# PiedPiper.net
KiCad netlist of a schematic drawn in EAGLE
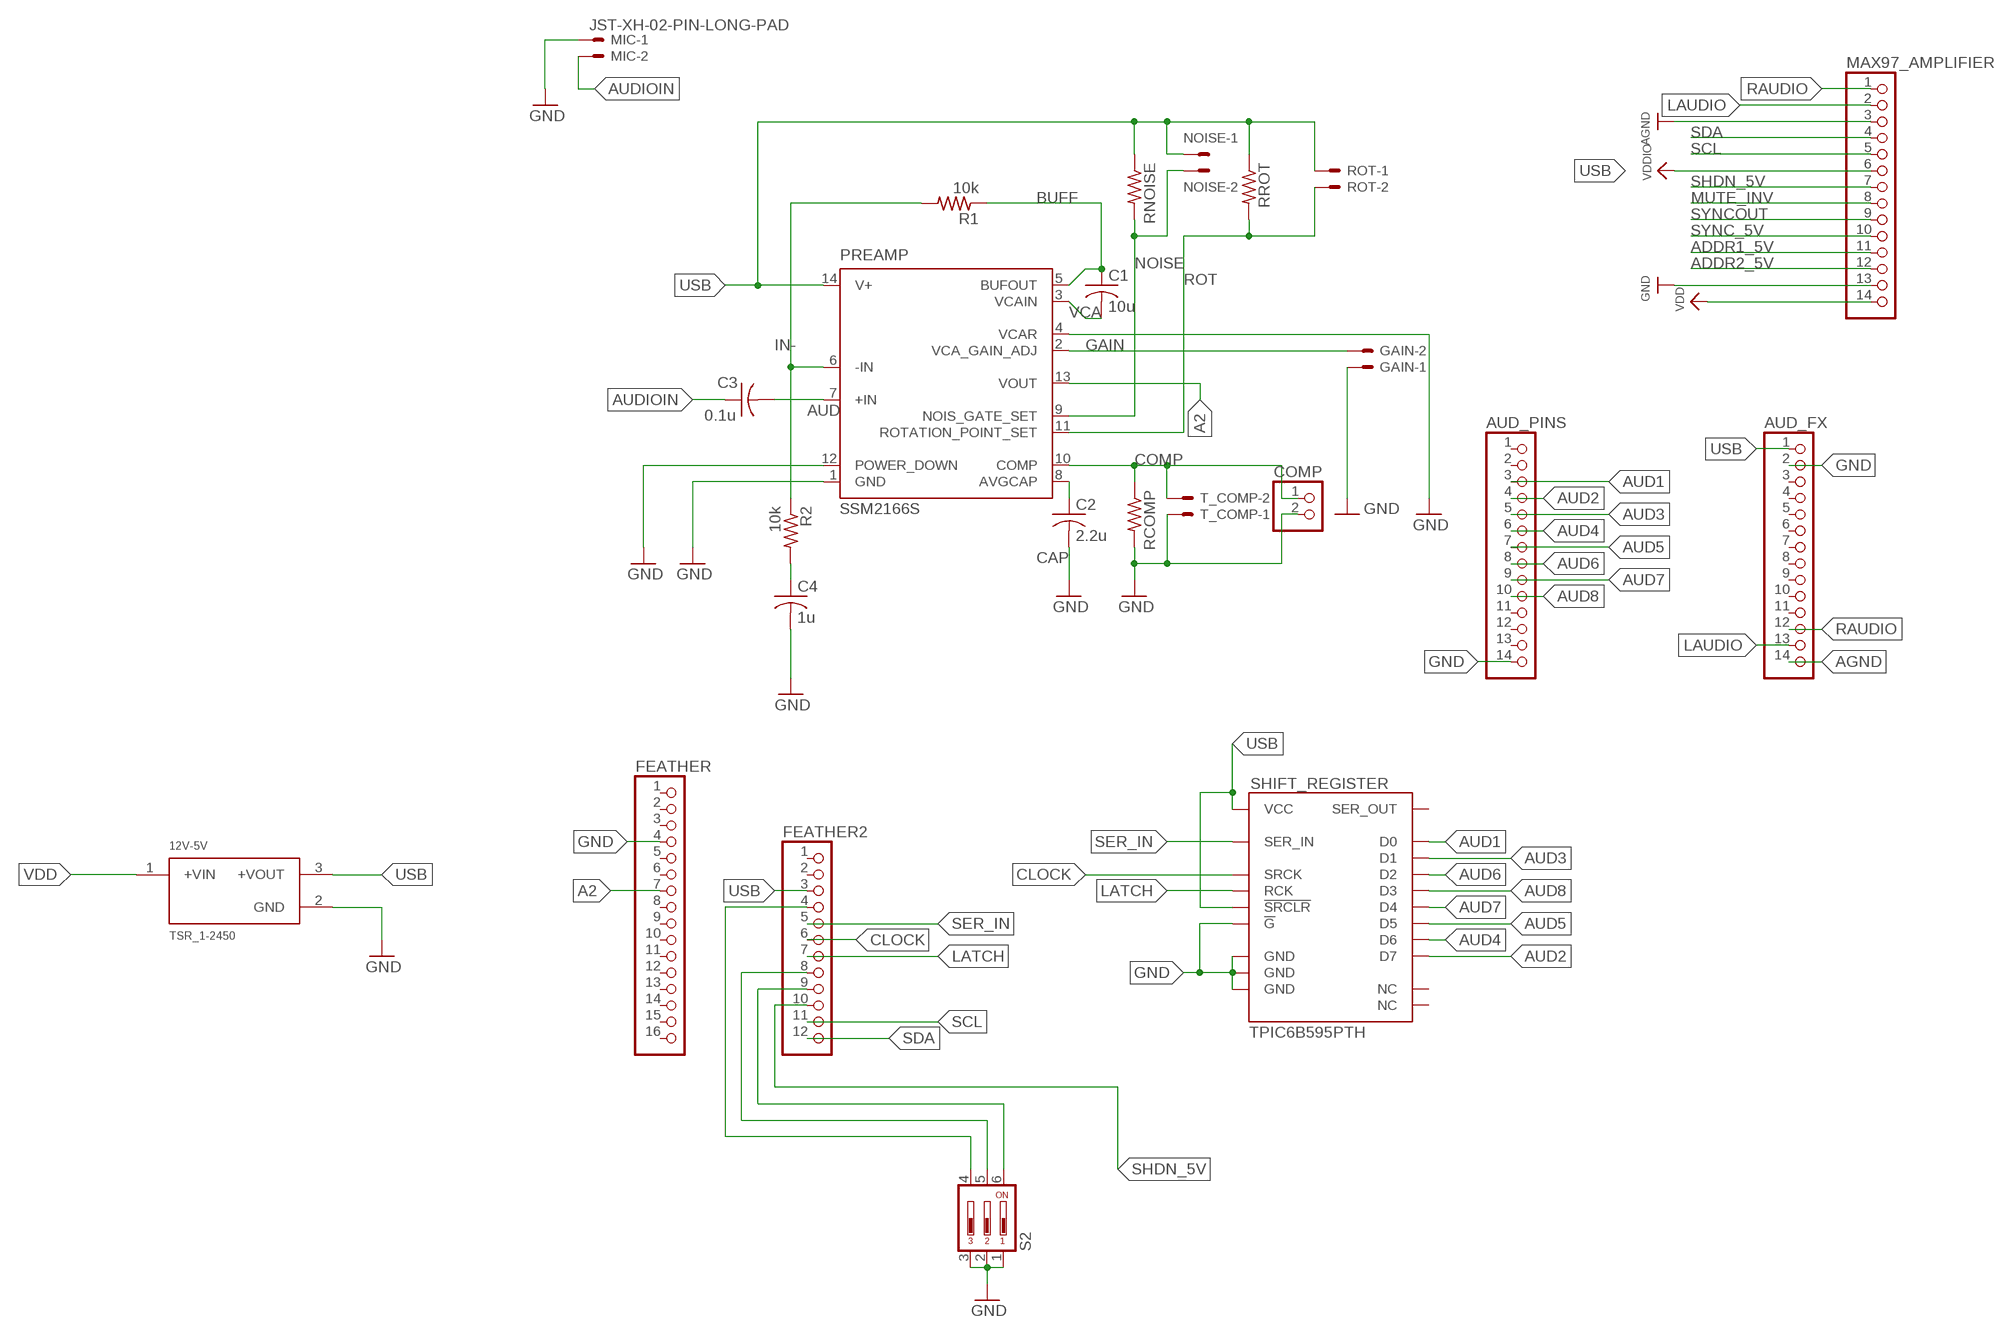
[diagram p0: schematic, sheet 1]

(export (version "E")
  (design (tool "Eeschema 10.0.6"))
  (components
    (comp (ref "12V-5V")
      (value "TSR_1-2450")
      (footprint "eagle-import:CONV_TSR_1-2450")
      (fields (field (name "MF") "Traco Power") (field (name "MP") "TSR 1-2450"))
      (libsource (lib "eagle-import") (part "TSR_1-2450"))
    )
    (comp (ref "AUD_FX")
      (value "PINHD-1X14")
      (footprint "eagle-import:1X14")
      (libsource (lib "eagle-import") (part "PINHD-1X14"))
    )
    (comp (ref "AUD_PINS")
      (value "PINHD-1X14")
      (footprint "eagle-import:1X14")
      (libsource (lib "eagle-import") (part "PINHD-1X14"))
    )
    (comp (ref "C1")
      (value "10u")
      (footprint "eagle-import:C0805")
      (libsource (lib "eagle-import") (part "C-USC0805"))
    )
    (comp (ref "C2")
      (value "2.2u")
      (footprint "eagle-import:C0805")
      (libsource (lib "eagle-import") (part "C-USC0805"))
    )
    (comp (ref "C3")
      (value "0.1u")
      (footprint "eagle-import:C0805")
      (libsource (lib "eagle-import") (part "C-USC0805"))
    )
    (comp (ref "C4")
      (value "1u")
      (footprint "eagle-import:C0805")
      (libsource (lib "eagle-import") (part "C-USC0805"))
    )
    (comp (ref "COMP")
      (value "PINHD-1X2")
      (footprint "eagle-import:1X02")
      (libsource (lib "eagle-import") (part "PINHD-1X2"))
    )
    (comp (ref "FEATHER")
      (value "PINHD-1X16")
      (footprint "eagle-import:1X16")
      (libsource (lib "eagle-import") (part "PINHD-1X16"))
    )
    (comp (ref "FEATHER2")
      (value "PINHD-1X12")
      (footprint "eagle-import:1X12")
      (libsource (lib "eagle-import") (part "PINHD-1X12"))
    )
    (comp (ref "GAIN")
      (value "JST-XH-02-PIN-LONG-PAD")
      (footprint "eagle-import:JST-XH-02-PACKAGE-LONG-PAD")
      (libsource (lib "eagle-import") (part "JST-XH-02-PIN-LONG-PAD"))
    )
    (comp (ref "MAX97_AMPLIFIER")
      (value "HEADER-1X14")
      (footprint "eagle-import:1X14_ROUND70")
      (libsource (lib "eagle-import") (part "HEADER-1X14"))
    )
    (comp (ref "MIC")
      (value "JST-XH-02-PIN-LONG-PAD")
      (footprint "eagle-import:JST-XH-02-PACKAGE-LONG-PAD")
      (libsource (lib "eagle-import") (part "JST-XH-02-PIN-LONG-PAD"))
    )
    (comp (ref "NOISE")
      (value "JST-XH-02-PIN-LONG-PAD")
      (footprint "eagle-import:JST-XH-02-PACKAGE-LONG-PAD")
      (libsource (lib "eagle-import") (part "JST-XH-02-PIN-LONG-PAD"))
    )
    (comp (ref "PREAMP")
      (value "SSM2166S")
      (footprint "eagle-import:SO14")
      (fields (field (name "MF") "Analog Devices") (field (name "MP") "SSM2166"))
      (libsource (lib "eagle-import") (part "SSM2166S"))
    )
    (comp (ref "R1")
      (value "10k")
      (footprint "eagle-import:R1206")
      (libsource (lib "eagle-import") (part "R-US_R1206"))
    )
    (comp (ref "R2")
      (value "10k")
      (footprint "eagle-import:R1206")
      (libsource (lib "eagle-import") (part "R-US_R1206"))
    )
    (comp (ref "RCOMP")
      (value "R-US_R1206")
      (footprint "eagle-import:R1206")
      (libsource (lib "eagle-import") (part "R-US_R1206"))
    )
    (comp (ref "RNOISE")
      (value "R-US_R1206")
      (footprint "eagle-import:R1206")
      (libsource (lib "eagle-import") (part "R-US_R1206"))
    )
    (comp (ref "ROT")
      (value "JST-XH-02-PIN-LONG-PAD")
      (footprint "eagle-import:JST-XH-02-PACKAGE-LONG-PAD")
      (libsource (lib "eagle-import") (part "JST-XH-02-PIN-LONG-PAD"))
    )
    (comp (ref "RROT")
      (value "R-US_R1206")
      (footprint "eagle-import:R1206")
      (libsource (lib "eagle-import") (part "R-US_R1206"))
    )
    (comp (ref "S2")
      (value "DP03")
      (footprint "eagle-import:DP-03")
      (fields (field (name "MPN") "MCDP03"))
      (libsource (lib "eagle-import") (part "DP03"))
    )
    (comp (ref "SHIFT_REGISTER")
      (value "TPIC6B595PTH")
      (footprint "eagle-import:DIL20")
      (fields (field (name "MF") "Texas Instruments") (field (name "MP") "TPIC6B595"))
      (libsource (lib "eagle-import") (part "TPIC6B595PTH"))
    )
    (comp (ref "T_COMP")
      (value "JST-XH-02-PIN-LONG-PAD")
      (footprint "eagle-import:JST-XH-02-PACKAGE-LONG-PAD")
      (libsource (lib "eagle-import") (part "JST-XH-02-PIN-LONG-PAD"))
    )
  )
  (nets
    (net (code "1") (name "/ADDR1_5V") (class "Default")
      (node (ref "MAX97_AMPLIFIER") (pin "11") (pinfunction "11_11") (pintype "passive"))
    )
    (net (code "2") (name "/ADDR2_5V") (class "Default")
      (node (ref "MAX97_AMPLIFIER") (pin "12") (pinfunction "12_12") (pintype "passive"))
    )
    (net (code "3") (name "/AUD") (class "Default")
      (node (ref "C3") (pin "2") (pinfunction "2_2") (pintype "passive"))
      (node (ref "PREAMP") (pin "7") (pinfunction "+IN_7") (pintype "input"))
    )
    (net (code "4") (name "/BUFF") (class "Default")
      (node (ref "C1") (pin "1") (pinfunction "1_1") (pintype "passive"))
      (node (ref "PREAMP") (pin "5") (pinfunction "BUFOUT_5") (pintype "output"))
      (node (ref "R1") (pin "1") (pinfunction "1_1") (pintype "passive"))
    )
    (net (code "5") (name "/CAP") (class "Default")
      (node (ref "C2") (pin "1") (pinfunction "1_1") (pintype "passive"))
      (node (ref "PREAMP") (pin "8") (pinfunction "AVGCAP_8") (pintype "passive"))
    )
    (net (code "6") (name "/COMP") (class "Default")
      (node (ref "COMP") (pin "1") (pinfunction "1_1") (pintype "passive"))
      (node (ref "PREAMP") (pin "10") (pinfunction "COMP_10") (pintype "passive"))
      (node (ref "RCOMP") (pin "1") (pinfunction "1_1") (pintype "passive"))
      (node (ref "T_COMP") (pin "2") (pinfunction "S_2") (pintype "passive"))
    )
    (net (code "7") (name "/GAIN") (class "Default")
      (node (ref "GAIN") (pin "2") (pinfunction "S_2") (pintype "passive"))
      (node (ref "PREAMP") (pin "2") (pinfunction "VCA_GAIN_ADJ_2") (pintype "input"))
    )
    (net (code "8") (name "/IN-") (class "Default")
      (node (ref "PREAMP") (pin "6") (pinfunction "-IN_6") (pintype "input"))
      (node (ref "R1") (pin "2") (pinfunction "2_2") (pintype "passive"))
      (node (ref "R2") (pin "1") (pinfunction "1_1") (pintype "passive"))
    )
    (net (code "9") (name "/MUTE_INV") (class "Default")
      (node (ref "MAX97_AMPLIFIER") (pin "8") (pinfunction "8_8") (pintype "passive"))
    )
    (net (code "10") (name "/NOISE") (class "Default")
      (node (ref "NOISE") (pin "2") (pinfunction "S_2") (pintype "passive"))
      (node (ref "PREAMP") (pin "9") (pinfunction "NOIS_GATE_SET_9") (pintype "passive"))
      (node (ref "RNOISE") (pin "2") (pinfunction "2_2") (pintype "passive"))
    )
    (net (code "11") (name "/ROT") (class "Default")
      (node (ref "PREAMP") (pin "11") (pinfunction "ROTATION_POINT_SET_11") (pintype "passive"))
      (node (ref "ROT") (pin "2") (pinfunction "S_2") (pintype "passive"))
      (node (ref "RROT") (pin "2") (pinfunction "2_2") (pintype "passive"))
    )
    (net (code "12") (name "/SYNCOUT") (class "Default")
      (node (ref "MAX97_AMPLIFIER") (pin "9") (pinfunction "9_9") (pintype "passive"))
    )
    (net (code "13") (name "/SYNC_5V") (class "Default")
      (node (ref "MAX97_AMPLIFIER") (pin "10") (pinfunction "10_10") (pintype "passive"))
    )
    (net (code "14") (name "/VCA") (class "Default")
      (node (ref "C1") (pin "2") (pinfunction "2_2") (pintype "passive"))
      (node (ref "PREAMP") (pin "3") (pinfunction "VCAIN_3") (pintype "input"))
    )
    (net (code "15") (name "A2") (class "Default")
      (node (ref "FEATHER") (pin "7") (pinfunction "7_7") (pintype "passive"))
      (node (ref "PREAMP") (pin "13") (pinfunction "VOUT_13") (pintype "output"))
    )
    (net (code "16") (name "AGND") (class "Default")
      (node (ref "AUD_FX") (pin "14") (pinfunction "14_14") (pintype "passive"))
      (node (ref "MAX97_AMPLIFIER") (pin "3") (pinfunction "3_3") (pintype "passive"))
    )
    (net (code "17") (name "AUD1") (class "Default")
      (node (ref "AUD_PINS") (pin "3") (pinfunction "3_3") (pintype "passive"))
      (node (ref "SHIFT_REGISTER") (pin "4") (pinfunction "D0_4") (pintype "output"))
    )
    (net (code "18") (name "AUD2") (class "Default")
      (node (ref "AUD_PINS") (pin "4") (pinfunction "4_4") (pintype "passive"))
      (node (ref "SHIFT_REGISTER") (pin "17") (pinfunction "D7_17") (pintype "output"))
    )
    (net (code "19") (name "AUD3") (class "Default")
      (node (ref "AUD_PINS") (pin "5") (pinfunction "5_5") (pintype "passive"))
      (node (ref "SHIFT_REGISTER") (pin "5") (pinfunction "D1_5") (pintype "output"))
    )
    (net (code "20") (name "AUD4") (class "Default")
      (node (ref "AUD_PINS") (pin "6") (pinfunction "6_6") (pintype "passive"))
      (node (ref "SHIFT_REGISTER") (pin "16") (pinfunction "D6_16") (pintype "output"))
    )
    (net (code "21") (name "AUD5") (class "Default")
      (node (ref "AUD_PINS") (pin "7") (pinfunction "7_7") (pintype "passive"))
      (node (ref "SHIFT_REGISTER") (pin "15") (pinfunction "D5_15") (pintype "output"))
    )
    (net (code "22") (name "AUD6") (class "Default")
      (node (ref "AUD_PINS") (pin "8") (pinfunction "8_8") (pintype "passive"))
      (node (ref "SHIFT_REGISTER") (pin "6") (pinfunction "D2_6") (pintype "output"))
    )
    (net (code "23") (name "AUD7") (class "Default")
      (node (ref "AUD_PINS") (pin "9") (pinfunction "9_9") (pintype "passive"))
      (node (ref "SHIFT_REGISTER") (pin "14") (pinfunction "D4_14") (pintype "output"))
    )
    (net (code "24") (name "AUD8") (class "Default")
      (node (ref "AUD_PINS") (pin "10") (pinfunction "10_10") (pintype "passive"))
      (node (ref "SHIFT_REGISTER") (pin "7") (pinfunction "D3_7") (pintype "output"))
    )
    (net (code "25") (name "AUDIOIN") (class "Default")
      (node (ref "C3") (pin "1") (pinfunction "1_1") (pintype "passive"))
      (node (ref "MIC") (pin "2") (pinfunction "S_2") (pintype "passive"))
    )
    (net (code "26") (name "CLOCK") (class "Default")
      (node (ref "FEATHER2") (pin "6") (pinfunction "6_6") (pintype "passive"))
      (node (ref "SHIFT_REGISTER") (pin "13") (pinfunction "SRCK_13") (pintype "input"))
    )
    (net (code "27") (name "GND") (class "Default")
      (node (ref "12V-5V") (pin "2") (pinfunction "GND_2") (pintype "power_in"))
      (node (ref "AUD_FX") (pin "2") (pinfunction "2_2") (pintype "passive"))
      (node (ref "AUD_PINS") (pin "14") (pinfunction "14_14") (pintype "passive"))
      (node (ref "C2") (pin "2") (pinfunction "2_2") (pintype "passive"))
      (node (ref "C4") (pin "2") (pinfunction "2_2") (pintype "passive"))
      (node (ref "COMP") (pin "2") (pinfunction "2_2") (pintype "passive"))
      (node (ref "FEATHER") (pin "4") (pinfunction "4_4") (pintype "passive"))
      (node (ref "GAIN") (pin "1") (pinfunction "S_1") (pintype "passive"))
      (node (ref "MAX97_AMPLIFIER") (pin "13") (pinfunction "13_13") (pintype "passive"))
      (node (ref "MIC") (pin "1") (pinfunction "S_1") (pintype "passive"))
      (node (ref "PREAMP") (pin "1") (pinfunction "GND_1") (pintype "power_in"))
      (node (ref "PREAMP") (pin "12") (pinfunction "POWER_DOWN_12") (pintype "input"))
      (node (ref "PREAMP") (pin "4") (pinfunction "VCAR_4") (pintype "input"))
      (node (ref "RCOMP") (pin "2") (pinfunction "2_2") (pintype "passive"))
      (node (ref "S2") (pin "1") (pinfunction "1_1") (pintype "passive"))
      (node (ref "S2") (pin "2") (pinfunction "2_2") (pintype "passive"))
      (node (ref "S2") (pin "3") (pinfunction "3_3") (pintype "passive"))
      (node (ref "SHIFT_REGISTER") (pin "10") (pinfunction "GND_10") (pintype "power_in"))
      (node (ref "SHIFT_REGISTER") (pin "11") (pinfunction "GND_11") (pintype "power_in"))
      (node (ref "SHIFT_REGISTER") (pin "19") (pinfunction "GND_19") (pintype "power_in"))
      (node (ref "SHIFT_REGISTER") (pin "9") (pinfunction "~{G}_9") (pintype "input"))
      (node (ref "T_COMP") (pin "1") (pinfunction "S_1") (pintype "passive"))
    )
    (net (code "28") (name "LATCH") (class "Default")
      (node (ref "FEATHER2") (pin "7") (pinfunction "7_7") (pintype "passive"))
      (node (ref "SHIFT_REGISTER") (pin "12") (pinfunction "RCK_12") (pintype "input"))
    )
    (net (code "29") (name "LAUDIO") (class "Default")
      (node (ref "AUD_FX") (pin "13") (pinfunction "13_13") (pintype "passive"))
      (node (ref "MAX97_AMPLIFIER") (pin "2") (pinfunction "2_2") (pintype "passive"))
    )
    (net (code "30") (name "Net-(C4-Pad1)") (class "Default")
      (node (ref "C4") (pin "1") (pinfunction "1_1") (pintype "passive"))
      (node (ref "R2") (pin "2") (pinfunction "2_2") (pintype "passive"))
    )
    (net (code "31") (name "Net-(FEATHER2-Pad4)") (class "Default")
      (node (ref "FEATHER2") (pin "4") (pinfunction "4_4") (pintype "passive"))
      (node (ref "S2") (pin "4") (pinfunction "4_4") (pintype "passive"))
    )
    (net (code "32") (name "Net-(FEATHER2-Pad8)") (class "Default")
      (node (ref "FEATHER2") (pin "8") (pinfunction "8_8") (pintype "passive"))
      (node (ref "S2") (pin "5") (pinfunction "5_5") (pintype "passive"))
    )
    (net (code "33") (name "Net-(FEATHER2-Pad9)") (class "Default")
      (node (ref "FEATHER2") (pin "9") (pinfunction "9_9") (pintype "passive"))
      (node (ref "S2") (pin "6") (pinfunction "6_6") (pintype "passive"))
    )
    (net (code "34") (name "RAUDIO") (class "Default")
      (node (ref "AUD_FX") (pin "12") (pinfunction "12_12") (pintype "passive"))
      (node (ref "MAX97_AMPLIFIER") (pin "1") (pinfunction "1_1") (pintype "passive"))
    )
    (net (code "35") (name "SCL") (class "Default")
      (node (ref "FEATHER2") (pin "11") (pinfunction "11_11") (pintype "passive"))
      (node (ref "MAX97_AMPLIFIER") (pin "5") (pinfunction "5_5") (pintype "passive"))
    )
    (net (code "36") (name "SDA") (class "Default")
      (node (ref "FEATHER2") (pin "12") (pinfunction "12_12") (pintype "passive"))
      (node (ref "MAX97_AMPLIFIER") (pin "4") (pinfunction "4_4") (pintype "passive"))
    )
    (net (code "37") (name "SER_IN") (class "Default")
      (node (ref "FEATHER2") (pin "5") (pinfunction "5_5") (pintype "passive"))
      (node (ref "SHIFT_REGISTER") (pin "3") (pinfunction "SER_IN_3") (pintype "input"))
    )
    (net (code "38") (name "SHDN_5V") (class "Default")
      (node (ref "FEATHER2") (pin "10") (pinfunction "10_10") (pintype "passive"))
      (node (ref "MAX97_AMPLIFIER") (pin "7") (pinfunction "7_7") (pintype "passive"))
    )
    (net (code "39") (name "USB") (class "Default")
      (node (ref "12V-5V") (pin "3") (pinfunction "+VOUT_3") (pintype "output"))
      (node (ref "AUD_FX") (pin "1") (pinfunction "1_1") (pintype "passive"))
      (node (ref "FEATHER2") (pin "3") (pinfunction "3_3") (pintype "passive"))
      (node (ref "MAX97_AMPLIFIER") (pin "6") (pinfunction "6_6") (pintype "passive"))
      (node (ref "NOISE") (pin "1") (pinfunction "S_1") (pintype "passive"))
      (node (ref "PREAMP") (pin "14") (pinfunction "V+_14") (pintype "power_in"))
      (node (ref "RNOISE") (pin "1") (pinfunction "1_1") (pintype "passive"))
      (node (ref "ROT") (pin "1") (pinfunction "S_1") (pintype "passive"))
      (node (ref "RROT") (pin "1") (pinfunction "1_1") (pintype "passive"))
      (node (ref "SHIFT_REGISTER") (pin "2") (pinfunction "VCC_2") (pintype "power_in"))
      (node (ref "SHIFT_REGISTER") (pin "8") (pinfunction "~{SRCLR}_8") (pintype "input"))
    )
    (net (code "40") (name "VDD") (class "Default")
      (node (ref "12V-5V") (pin "1") (pinfunction "+VIN_1") (pintype "input"))
      (node (ref "MAX97_AMPLIFIER") (pin "14") (pinfunction "14_14") (pintype "passive"))
    )
    (net (code "41") (name "unconnected-(AUD_FX-Pad3)") (class "Default")
      (node (ref "AUD_FX") (pin "3") (pinfunction "3_3") (pintype "passive"))
    )
    (net (code "42") (name "unconnected-(AUD_FX-Pad4)") (class "Default")
      (node (ref "AUD_FX") (pin "4") (pinfunction "4_4") (pintype "passive"))
    )
    (net (code "43") (name "unconnected-(AUD_FX-Pad5)") (class "Default")
      (node (ref "AUD_FX") (pin "5") (pinfunction "5_5") (pintype "passive"))
    )
    (net (code "44") (name "unconnected-(AUD_FX-Pad6)") (class "Default")
      (node (ref "AUD_FX") (pin "6") (pinfunction "6_6") (pintype "passive"))
    )
    (net (code "45") (name "unconnected-(AUD_FX-Pad7)") (class "Default")
      (node (ref "AUD_FX") (pin "7") (pinfunction "7_7") (pintype "passive"))
    )
    (net (code "46") (name "unconnected-(AUD_FX-Pad8)") (class "Default")
      (node (ref "AUD_FX") (pin "8") (pinfunction "8_8") (pintype "passive"))
    )
    (net (code "47") (name "unconnected-(AUD_FX-Pad9)") (class "Default")
      (node (ref "AUD_FX") (pin "9") (pinfunction "9_9") (pintype "passive"))
    )
    (net (code "48") (name "unconnected-(AUD_FX-Pad10)") (class "Default")
      (node (ref "AUD_FX") (pin "10") (pinfunction "10_10") (pintype "passive"))
    )
    (net (code "49") (name "unconnected-(AUD_FX-Pad11)") (class "Default")
      (node (ref "AUD_FX") (pin "11") (pinfunction "11_11") (pintype "passive"))
    )
    (net (code "50") (name "unconnected-(AUD_PINS-Pad1)") (class "Default")
      (node (ref "AUD_PINS") (pin "1") (pinfunction "1_1") (pintype "passive"))
    )
    (net (code "51") (name "unconnected-(AUD_PINS-Pad2)") (class "Default")
      (node (ref "AUD_PINS") (pin "2") (pinfunction "2_2") (pintype "passive"))
    )
    (net (code "52") (name "unconnected-(AUD_PINS-Pad11)") (class "Default")
      (node (ref "AUD_PINS") (pin "11") (pinfunction "11_11") (pintype "passive"))
    )
    (net (code "53") (name "unconnected-(AUD_PINS-Pad12)") (class "Default")
      (node (ref "AUD_PINS") (pin "12") (pinfunction "12_12") (pintype "passive"))
    )
    (net (code "54") (name "unconnected-(AUD_PINS-Pad13)") (class "Default")
      (node (ref "AUD_PINS") (pin "13") (pinfunction "13_13") (pintype "passive"))
    )
    (net (code "55") (name "unconnected-(FEATHER-Pad1)") (class "Default")
      (node (ref "FEATHER") (pin "1") (pinfunction "1_1") (pintype "passive"))
    )
    (net (code "56") (name "unconnected-(FEATHER-Pad2)") (class "Default")
      (node (ref "FEATHER") (pin "2") (pinfunction "2_2") (pintype "passive"))
    )
    (net (code "57") (name "unconnected-(FEATHER-Pad3)") (class "Default")
      (node (ref "FEATHER") (pin "3") (pinfunction "3_3") (pintype "passive"))
    )
    (net (code "58") (name "unconnected-(FEATHER-Pad5)") (class "Default")
      (node (ref "FEATHER") (pin "5") (pinfunction "5_5") (pintype "passive"))
    )
    (net (code "59") (name "unconnected-(FEATHER-Pad6)") (class "Default")
      (node (ref "FEATHER") (pin "6") (pinfunction "6_6") (pintype "passive"))
    )
    (net (code "60") (name "unconnected-(FEATHER-Pad8)") (class "Default")
      (node (ref "FEATHER") (pin "8") (pinfunction "8_8") (pintype "passive"))
    )
    (net (code "61") (name "unconnected-(FEATHER-Pad9)") (class "Default")
      (node (ref "FEATHER") (pin "9") (pinfunction "9_9") (pintype "passive"))
    )
    (net (code "62") (name "unconnected-(FEATHER-Pad10)") (class "Default")
      (node (ref "FEATHER") (pin "10") (pinfunction "10_10") (pintype "passive"))
    )
    (net (code "63") (name "unconnected-(FEATHER-Pad11)") (class "Default")
      (node (ref "FEATHER") (pin "11") (pinfunction "11_11") (pintype "passive"))
    )
    (net (code "64") (name "unconnected-(FEATHER-Pad12)") (class "Default")
      (node (ref "FEATHER") (pin "12") (pinfunction "12_12") (pintype "passive"))
    )
    (net (code "65") (name "unconnected-(FEATHER-Pad13)") (class "Default")
      (node (ref "FEATHER") (pin "13") (pinfunction "13_13") (pintype "passive"))
    )
    (net (code "66") (name "unconnected-(FEATHER-Pad14)") (class "Default")
      (node (ref "FEATHER") (pin "14") (pinfunction "14_14") (pintype "passive"))
    )
    (net (code "67") (name "unconnected-(FEATHER-Pad15)") (class "Default")
      (node (ref "FEATHER") (pin "15") (pinfunction "15_15") (pintype "passive"))
    )
    (net (code "68") (name "unconnected-(FEATHER-Pad16)") (class "Default")
      (node (ref "FEATHER") (pin "16") (pinfunction "16_16") (pintype "passive"))
    )
    (net (code "69") (name "unconnected-(FEATHER2-Pad1)") (class "Default")
      (node (ref "FEATHER2") (pin "1") (pinfunction "1_1") (pintype "passive"))
    )
    (net (code "70") (name "unconnected-(FEATHER2-Pad2)") (class "Default")
      (node (ref "FEATHER2") (pin "2") (pinfunction "2_2") (pintype "passive"))
    )
    (net (code "71") (name "unconnected-(SHIFT_REGISTER-NC-Pad1)") (class "Default")
      (node (ref "SHIFT_REGISTER") (pin "1") (pinfunction "NC_1") (pintype "no_connect"))
    )
    (net (code "72") (name "unconnected-(SHIFT_REGISTER-NC-Pad20)") (class "Default")
      (node (ref "SHIFT_REGISTER") (pin "20") (pinfunction "NC_20") (pintype "no_connect"))
    )
    (net (code "73") (name "unconnected-(SHIFT_REGISTER-SER_OUT-Pad18)") (class "Default")
      (node (ref "SHIFT_REGISTER") (pin "18") (pinfunction "SER_OUT_18") (pintype "output"))
    )
  )
)
